# Peripheral_Circuit_B.net
KiCad netlist of a schematic drawn in Altium Designer
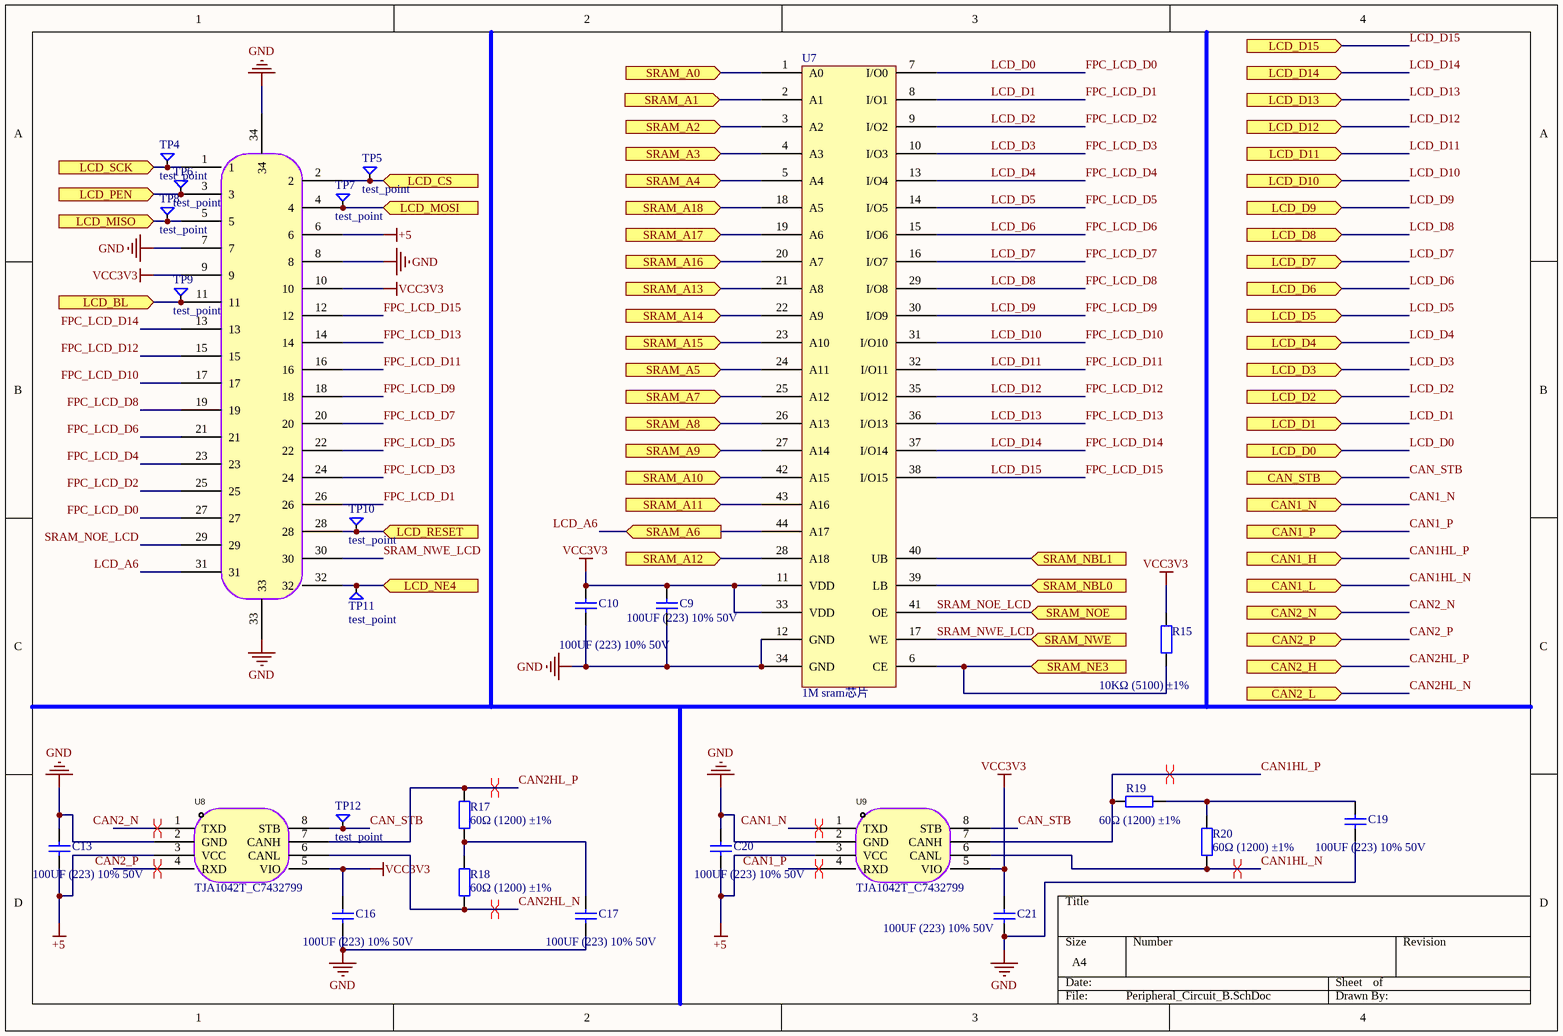
[diagram p0: Peripheral_Circuit_B.SchDoc]

(export (version "E")
  (design (tool "Eeschema 10.0.6"))
  (components
    (comp (ref "C9")
      (value "100UF (223) 10% 50V")
      (footprint "0805_C")
      (description "贴片电容")
      (libsource (lib "Miscellaneous Devices LC") (part "0805 22nF (223) 10% 50V"))
    )
    (comp (ref "C10")
      (value "100UF (223) 10% 50V")
      (footprint "0805_C")
      (description "贴片电容")
      (libsource (lib "Miscellaneous Devices LC") (part "0805 22nF (223) 10% 50V"))
    )
    (comp (ref "C13")
      (value "100UF (223) 10% 50V")
      (footprint "0805_C")
      (description "贴片电容")
      (libsource (lib "Miscellaneous Devices LC") (part "0805 22nF (223) 10% 50V"))
    )
    (comp (ref "C16")
      (value "100UF (223) 10% 50V")
      (footprint "0805_C")
      (description "贴片电容")
      (libsource (lib "Miscellaneous Devices LC") (part "0805 22nF (223) 10% 50V"))
    )
    (comp (ref "C17")
      (value "100UF (223) 10% 50V")
      (footprint "0805_C")
      (description "贴片电容")
      (libsource (lib "Miscellaneous Devices LC") (part "0805 22nF (223) 10% 50V"))
    )
    (comp (ref "C19")
      (value "100UF (223) 10% 50V")
      (footprint "0805_C")
      (description "贴片电容")
      (libsource (lib "Miscellaneous Devices LC") (part "0805 22nF (223) 10% 50V"))
    )
    (comp (ref "C20")
      (value "100UF (223) 10% 50V")
      (footprint "0805_C")
      (description "贴片电容")
      (libsource (lib "Miscellaneous Devices LC") (part "0805 22nF (223) 10% 50V"))
    )
    (comp (ref "C21")
      (value "100UF (223) 10% 50V")
      (footprint "0805_C")
      (description "贴片电容")
      (libsource (lib "Miscellaneous Devices LC") (part "0805 22nF (223) 10% 50V"))
    )
    (comp (ref "FPC1")
      (value "FPC-05F-32PH20")
      (footprint "FPC-SMD_32P-P0.50_XUNPU_FPC-05F-32PH20")
      (fields (field (name "MANUFACTURER") "XUNPU(讯普)"))
      (libsource (lib "EXTRA") (part "FPC-05F-32PH20"))
    )
    (comp (ref "R15")
      (value "10KΩ (5100) ±1%")
      (footprint "0805_R")
      (description "贴片电阻")
      (libsource (lib "Miscellaneous Devices LC") (part "0805 510Ω (5100) 1%"))
    )
    (comp (ref "R17")
      (value "60Ω (1200) ±1%")
      (footprint "0805_R")
      (description "贴片电阻")
      (libsource (lib "Miscellaneous Devices LC") (part "0805 120Ω (1200) 1%"))
    )
    (comp (ref "R18")
      (value "60Ω (1200) ±1%")
      (footprint "0805_R")
      (description "贴片电阻")
      (libsource (lib "Miscellaneous Devices LC") (part "0805 120Ω (1200) 1%"))
    )
    (comp (ref "R19")
      (value "60Ω (1200) ±1%")
      (footprint "0805_R")
      (description "贴片电阻")
      (libsource (lib "") (part "0805 120Ω (1200) 1%_1"))
    )
    (comp (ref "R20")
      (value "60Ω (1200) ±1%")
      (footprint "0805_R")
      (description "贴片电阻")
      (libsource (lib "Miscellaneous Devices LC") (part "0805 120Ω (1200) 1%"))
    )
    (comp (ref "TP4")
      (value "test_point")
      (footprint "test_point")
      (description "测量点")
      (libsource (lib "EXTRA") (part "test_point"))
    )
    (comp (ref "TP5")
      (value "test_point")
      (footprint "test_point")
      (description "测量点")
      (libsource (lib "EXTRA") (part "test_point"))
    )
    (comp (ref "TP6")
      (value "test_point")
      (footprint "test_point")
      (description "测量点")
      (libsource (lib "EXTRA") (part "test_point"))
    )
    (comp (ref "TP7")
      (value "test_point")
      (footprint "test_point")
      (description "测量点")
      (libsource (lib "EXTRA") (part "test_point"))
    )
    (comp (ref "TP8")
      (value "test_point")
      (footprint "test_point")
      (description "测量点")
      (libsource (lib "EXTRA") (part "test_point"))
    )
    (comp (ref "TP9")
      (value "test_point")
      (footprint "test_point")
      (description "测量点")
      (libsource (lib "EXTRA") (part "test_point"))
    )
    (comp (ref "TP10")
      (value "test_point")
      (footprint "test_point")
      (description "测量点")
      (libsource (lib "EXTRA") (part "test_point"))
    )
    (comp (ref "TP11")
      (value "test_point")
      (footprint "test_point")
      (description "测量点")
      (libsource (lib "EXTRA") (part "test_point"))
    )
    (comp (ref "TP12")
      (value "test_point")
      (footprint "test_point")
      (description "测量点")
      (libsource (lib "EXTRA") (part "test_point"))
    )
    (comp (ref "U7")
      (value "1M sram芯片")
      (footprint "IS61LV51216")
      (description "外接SRAM芯片")
      (libsource (lib "EXTRA") (part "XM8A51216V33A"))
    )
    (comp (ref "U8")
      (value "TJA1042T_C7432799")
      (footprint "TJA1042")
      (fields (field (name "MANUFACTURER") "Tokmas(托克马斯)") (field (name "MANUFACTURER PART") "TJA1042T"))
      (libsource (lib "EXTRA") (part "TJA1042T_C7432799"))
    )
    (comp (ref "U9")
      (value "TJA1042T_C7432799")
      (footprint "TJA1042")
      (fields (field (name "MANUFACTURER") "Tokmas(托克马斯)") (field (name "MANUFACTURER PART") "TJA1042T"))
      (libsource (lib "EXTRA") (part "TJA1042T_C7432799"))
    )
  )
  (nets
    (net (code "1") (name "+5") (class "Default")
      (node (ref "C13") (pin "1") (pinfunction "1_1") (pintype "passive"))
      (node (ref "C20") (pin "1") (pinfunction "1_1") (pintype "passive"))
      (node (ref "FPC1") (pin "6") (pinfunction "6_6") (pintype "passive"))
      (node (ref "U8") (pin "3") (pinfunction "VCC_3") (pintype "passive"))
      (node (ref "U9") (pin "3") (pinfunction "VCC_3") (pintype "passive"))
    )
    (net (code "2") (name "/CAN1HL_N") (class "Default")
      (node (ref "R20") (pin "1") (pinfunction "1_1") (pintype "passive"))
      (node (ref "U9") (pin "6") (pinfunction "CANL_6") (pintype "passive"))
    )
    (net (code "3") (name "/CAN1HL_P") (class "Default")
      (node (ref "R19") (pin "2") (pinfunction "2_2") (pintype "passive"))
      (node (ref "U9") (pin "7") (pinfunction "CANH_7") (pintype "passive"))
    )
    (net (code "4") (name "/CAN1_N") (class "Default")
      (node (ref "U9") (pin "1") (pinfunction "TXD_1") (pintype "passive"))
    )
    (net (code "5") (name "/CAN1_P") (class "Default")
      (node (ref "U9") (pin "4") (pinfunction "RXD_4") (pintype "passive"))
    )
    (net (code "6") (name "/CAN2HL_N") (class "Default")
      (node (ref "R18") (pin "1") (pinfunction "1_1") (pintype "passive"))
      (node (ref "U8") (pin "6") (pinfunction "CANL_6") (pintype "passive"))
    )
    (net (code "7") (name "/CAN2HL_P") (class "Default")
      (node (ref "R17") (pin "2") (pinfunction "2_2") (pintype "passive"))
      (node (ref "U8") (pin "7") (pinfunction "CANH_7") (pintype "passive"))
    )
    (net (code "8") (name "/CAN2_N") (class "Default")
      (node (ref "U8") (pin "1") (pinfunction "TXD_1") (pintype "passive"))
    )
    (net (code "9") (name "/CAN2_P") (class "Default")
      (node (ref "U8") (pin "4") (pinfunction "RXD_4") (pintype "passive"))
    )
    (net (code "10") (name "/CAN_STB") (class "Default")
      (node (ref "TP12") (pin "1") (pinfunction "1_1") (pintype "passive"))
      (node (ref "U8") (pin "8") (pinfunction "STB_8") (pintype "passive"))
      (node (ref "U9") (pin "8") (pinfunction "STB_8") (pintype "passive"))
    )
    (net (code "11") (name "/FPC_LCD_D0") (class "Default")
      (node (ref "FPC1") (pin "27") (pinfunction "27_27") (pintype "passive"))
      (node (ref "U7") (pin "7") (pinfunction "I/O0_7") (pintype "passive"))
    )
    (net (code "12") (name "/FPC_LCD_D1") (class "Default")
      (node (ref "FPC1") (pin "26") (pinfunction "26_26") (pintype "passive"))
      (node (ref "U7") (pin "8") (pinfunction "I/O1_8") (pintype "passive"))
    )
    (net (code "13") (name "/FPC_LCD_D2") (class "Default")
      (node (ref "FPC1") (pin "25") (pinfunction "25_25") (pintype "passive"))
      (node (ref "U7") (pin "9") (pinfunction "I/O2_9") (pintype "passive"))
    )
    (net (code "14") (name "/FPC_LCD_D3") (class "Default")
      (node (ref "FPC1") (pin "24") (pinfunction "24_24") (pintype "passive"))
      (node (ref "U7") (pin "10") (pinfunction "I/O3_10") (pintype "passive"))
    )
    (net (code "15") (name "/FPC_LCD_D4") (class "Default")
      (node (ref "FPC1") (pin "23") (pinfunction "23_23") (pintype "passive"))
      (node (ref "U7") (pin "13") (pinfunction "I/O4_13") (pintype "passive"))
    )
    (net (code "16") (name "/FPC_LCD_D5") (class "Default")
      (node (ref "FPC1") (pin "22") (pinfunction "22_22") (pintype "passive"))
      (node (ref "U7") (pin "14") (pinfunction "I/O5_14") (pintype "passive"))
    )
    (net (code "17") (name "/FPC_LCD_D6") (class "Default")
      (node (ref "FPC1") (pin "21") (pinfunction "21_21") (pintype "passive"))
      (node (ref "U7") (pin "15") (pinfunction "I/O6_15") (pintype "passive"))
    )
    (net (code "18") (name "/FPC_LCD_D7") (class "Default")
      (node (ref "FPC1") (pin "20") (pinfunction "20_20") (pintype "passive"))
      (node (ref "U7") (pin "16") (pinfunction "I/O7_16") (pintype "passive"))
    )
    (net (code "19") (name "/FPC_LCD_D8") (class "Default")
      (node (ref "FPC1") (pin "19") (pinfunction "19_19") (pintype "passive"))
      (node (ref "U7") (pin "29") (pinfunction "I/O8_29") (pintype "passive"))
    )
    (net (code "20") (name "/FPC_LCD_D9") (class "Default")
      (node (ref "FPC1") (pin "18") (pinfunction "18_18") (pintype "passive"))
      (node (ref "U7") (pin "30") (pinfunction "I/O9_30") (pintype "passive"))
    )
    (net (code "21") (name "/FPC_LCD_D10") (class "Default")
      (node (ref "FPC1") (pin "17") (pinfunction "17_17") (pintype "passive"))
      (node (ref "U7") (pin "31") (pinfunction "I/O10_31") (pintype "passive"))
    )
    (net (code "22") (name "/FPC_LCD_D11") (class "Default")
      (node (ref "FPC1") (pin "16") (pinfunction "16_16") (pintype "passive"))
      (node (ref "U7") (pin "32") (pinfunction "I/O11_32") (pintype "passive"))
    )
    (net (code "23") (name "/FPC_LCD_D12") (class "Default")
      (node (ref "FPC1") (pin "15") (pinfunction "15_15") (pintype "passive"))
      (node (ref "U7") (pin "35") (pinfunction "I/O12_35") (pintype "passive"))
    )
    (net (code "24") (name "/FPC_LCD_D13") (class "Default")
      (node (ref "FPC1") (pin "14") (pinfunction "14_14") (pintype "passive"))
      (node (ref "U7") (pin "36") (pinfunction "I/O13_36") (pintype "passive"))
    )
    (net (code "25") (name "/FPC_LCD_D14") (class "Default")
      (node (ref "FPC1") (pin "13") (pinfunction "13_13") (pintype "passive"))
      (node (ref "U7") (pin "37") (pinfunction "I/O14_37") (pintype "passive"))
    )
    (net (code "26") (name "/FPC_LCD_D15") (class "Default")
      (node (ref "FPC1") (pin "12") (pinfunction "12_12") (pintype "passive"))
      (node (ref "U7") (pin "38") (pinfunction "I/O15_38") (pintype "passive"))
    )
    (net (code "27") (name "/LCD_A6") (class "Default")
      (node (ref "FPC1") (pin "31") (pinfunction "31_31") (pintype "passive"))
      (node (ref "U7") (pin "44") (pinfunction "A17_44") (pintype "passive"))
    )
    (net (code "28") (name "/LCD_BL") (class "Default")
      (node (ref "FPC1") (pin "11") (pinfunction "11_11") (pintype "passive"))
      (node (ref "TP9") (pin "1") (pinfunction "1_1") (pintype "passive"))
    )
    (net (code "29") (name "/LCD_CS") (class "Default")
      (node (ref "FPC1") (pin "2") (pinfunction "2_2") (pintype "passive"))
      (node (ref "TP5") (pin "1") (pinfunction "1_1") (pintype "passive"))
    )
    (net (code "30") (name "/LCD_MISO") (class "Default")
      (node (ref "FPC1") (pin "5") (pinfunction "5_5") (pintype "passive"))
      (node (ref "TP8") (pin "1") (pinfunction "1_1") (pintype "passive"))
    )
    (net (code "31") (name "/LCD_MOSI") (class "Default")
      (node (ref "FPC1") (pin "4") (pinfunction "4_4") (pintype "passive"))
      (node (ref "TP7") (pin "1") (pinfunction "1_1") (pintype "passive"))
    )
    (net (code "32") (name "/LCD_NE4") (class "Default")
      (node (ref "FPC1") (pin "32") (pinfunction "32_32") (pintype "passive"))
      (node (ref "TP11") (pin "1") (pinfunction "1_1") (pintype "passive"))
    )
    (net (code "33") (name "/LCD_PEN") (class "Default")
      (node (ref "FPC1") (pin "3") (pinfunction "3_3") (pintype "passive"))
      (node (ref "TP6") (pin "1") (pinfunction "1_1") (pintype "passive"))
    )
    (net (code "34") (name "/LCD_RESET") (class "Default")
      (node (ref "FPC1") (pin "28") (pinfunction "28_28") (pintype "passive"))
      (node (ref "TP10") (pin "1") (pinfunction "1_1") (pintype "passive"))
    )
    (net (code "35") (name "/LCD_SCK") (class "Default")
      (node (ref "FPC1") (pin "1") (pinfunction "1_1") (pintype "passive"))
      (node (ref "TP4") (pin "1") (pinfunction "1_1") (pintype "passive"))
    )
    (net (code "36") (name "/SRAM_A0") (class "Default")
      (node (ref "U7") (pin "1") (pinfunction "A0_1") (pintype "passive"))
    )
    (net (code "37") (name "/SRAM_A1") (class "Default")
      (node (ref "U7") (pin "2") (pinfunction "A1_2") (pintype "passive"))
    )
    (net (code "38") (name "/SRAM_A2") (class "Default")
      (node (ref "U7") (pin "3") (pinfunction "A2_3") (pintype "passive"))
    )
    (net (code "39") (name "/SRAM_A3") (class "Default")
      (node (ref "U7") (pin "4") (pinfunction "A3_4") (pintype "passive"))
    )
    (net (code "40") (name "/SRAM_A4") (class "Default")
      (node (ref "U7") (pin "5") (pinfunction "A4_5") (pintype "passive"))
    )
    (net (code "41") (name "/SRAM_A5") (class "Default")
      (node (ref "U7") (pin "24") (pinfunction "A11_24") (pintype "passive"))
    )
    (net (code "42") (name "/SRAM_A7") (class "Default")
      (node (ref "U7") (pin "25") (pinfunction "A12_25") (pintype "passive"))
    )
    (net (code "43") (name "/SRAM_A8") (class "Default")
      (node (ref "U7") (pin "26") (pinfunction "A13_26") (pintype "passive"))
    )
    (net (code "44") (name "/SRAM_A9") (class "Default")
      (node (ref "U7") (pin "27") (pinfunction "A14_27") (pintype "passive"))
    )
    (net (code "45") (name "/SRAM_A10") (class "Default")
      (node (ref "U7") (pin "42") (pinfunction "A15_42") (pintype "passive"))
    )
    (net (code "46") (name "/SRAM_A11") (class "Default")
      (node (ref "U7") (pin "43") (pinfunction "A16_43") (pintype "passive"))
    )
    (net (code "47") (name "/SRAM_A12") (class "Default")
      (node (ref "U7") (pin "28") (pinfunction "A18_28") (pintype "passive"))
    )
    (net (code "48") (name "/SRAM_A13") (class "Default")
      (node (ref "U7") (pin "21") (pinfunction "A8_21") (pintype "passive"))
    )
    (net (code "49") (name "/SRAM_A14") (class "Default")
      (node (ref "U7") (pin "22") (pinfunction "A9_22") (pintype "passive"))
    )
    (net (code "50") (name "/SRAM_A15") (class "Default")
      (node (ref "U7") (pin "23") (pinfunction "A10_23") (pintype "passive"))
    )
    (net (code "51") (name "/SRAM_A16") (class "Default")
      (node (ref "U7") (pin "20") (pinfunction "A7_20") (pintype "passive"))
    )
    (net (code "52") (name "/SRAM_A17") (class "Default")
      (node (ref "U7") (pin "19") (pinfunction "A6_19") (pintype "passive"))
    )
    (net (code "53") (name "/SRAM_A18") (class "Default")
      (node (ref "U7") (pin "18") (pinfunction "A5_18") (pintype "passive"))
    )
    (net (code "54") (name "/SRAM_NBL0") (class "Default")
      (node (ref "U7") (pin "39") (pinfunction "LB_39") (pintype "passive"))
    )
    (net (code "55") (name "/SRAM_NBL1") (class "Default")
      (node (ref "U7") (pin "40") (pinfunction "UB_40") (pintype "passive"))
    )
    (net (code "56") (name "/SRAM_NE3") (class "Default")
      (node (ref "R15") (pin "1") (pinfunction "1_1") (pintype "passive"))
      (node (ref "U7") (pin "6") (pinfunction "CE_6") (pintype "passive"))
    )
    (net (code "57") (name "/SRAM_NOE_LCD") (class "Default")
      (node (ref "FPC1") (pin "29") (pinfunction "29_29") (pintype "passive"))
      (node (ref "U7") (pin "41") (pinfunction "OE_41") (pintype "passive"))
    )
    (net (code "58") (name "/SRAM_NWE_LCD") (class "Default")
      (node (ref "FPC1") (pin "30") (pinfunction "30_30") (pintype "passive"))
      (node (ref "U7") (pin "17") (pinfunction "WE_17") (pintype "passive"))
    )
    (net (code "59") (name "GND") (class "Default")
      (node (ref "C10") (pin "1") (pinfunction "1_1") (pintype "passive"))
      (node (ref "C13") (pin "2") (pinfunction "2_2") (pintype "passive"))
      (node (ref "C16") (pin "1") (pinfunction "1_1") (pintype "passive"))
      (node (ref "C17") (pin "1") (pinfunction "1_1") (pintype "passive"))
      (node (ref "C19") (pin "1") (pinfunction "1_1") (pintype "passive"))
      (node (ref "C20") (pin "2") (pinfunction "2_2") (pintype "passive"))
      (node (ref "C21") (pin "1") (pinfunction "1_1") (pintype "passive"))
      (node (ref "C9") (pin "1") (pinfunction "1_1") (pintype "passive"))
      (node (ref "FPC1") (pin "33") (pinfunction "33_33") (pintype "passive"))
      (node (ref "FPC1") (pin "34") (pinfunction "34_34") (pintype "passive"))
      (node (ref "FPC1") (pin "7") (pinfunction "7_7") (pintype "passive"))
      (node (ref "FPC1") (pin "8") (pinfunction "8_8") (pintype "passive"))
      (node (ref "U7") (pin "12") (pinfunction "GND_12") (pintype "passive"))
      (node (ref "U7") (pin "34") (pinfunction "GND_34") (pintype "passive"))
      (node (ref "U8") (pin "2") (pinfunction "GND_2") (pintype "passive"))
      (node (ref "U9") (pin "2") (pinfunction "GND_2") (pintype "passive"))
    )
    (net (code "60") (name "Net-(C17-Pad2)") (class "Default")
      (node (ref "C17") (pin "2") (pinfunction "2_2") (pintype "passive"))
      (node (ref "R17") (pin "1") (pinfunction "1_1") (pintype "passive"))
      (node (ref "R18") (pin "2") (pinfunction "2_2") (pintype "passive"))
    )
    (net (code "61") (name "Net-(C19-Pad2)") (class "Default")
      (node (ref "C19") (pin "2") (pinfunction "2_2") (pintype "passive"))
      (node (ref "R19") (pin "1") (pinfunction "1_1") (pintype "passive"))
      (node (ref "R20") (pin "2") (pinfunction "2_2") (pintype "passive"))
    )
    (net (code "62") (name "VCC3V3") (class "Default")
      (node (ref "C10") (pin "2") (pinfunction "2_2") (pintype "passive"))
      (node (ref "C16") (pin "2") (pinfunction "2_2") (pintype "passive"))
      (node (ref "C21") (pin "2") (pinfunction "2_2") (pintype "passive"))
      (node (ref "C9") (pin "2") (pinfunction "2_2") (pintype "passive"))
      (node (ref "FPC1") (pin "10") (pinfunction "10_10") (pintype "passive"))
      (node (ref "FPC1") (pin "9") (pinfunction "9_9") (pintype "passive"))
      (node (ref "R15") (pin "2") (pinfunction "2_2") (pintype "passive"))
      (node (ref "U7") (pin "11") (pinfunction "VDD_11") (pintype "passive"))
      (node (ref "U7") (pin "33") (pinfunction "VDD_33") (pintype "passive"))
      (node (ref "U8") (pin "5") (pinfunction "VIO_5") (pintype "passive"))
      (node (ref "U9") (pin "5") (pinfunction "VIO_5") (pintype "passive"))
    )
  )
)
